# IQ_Demodulator.net
KiCad netlist of a schematic drawn in Altium Designer
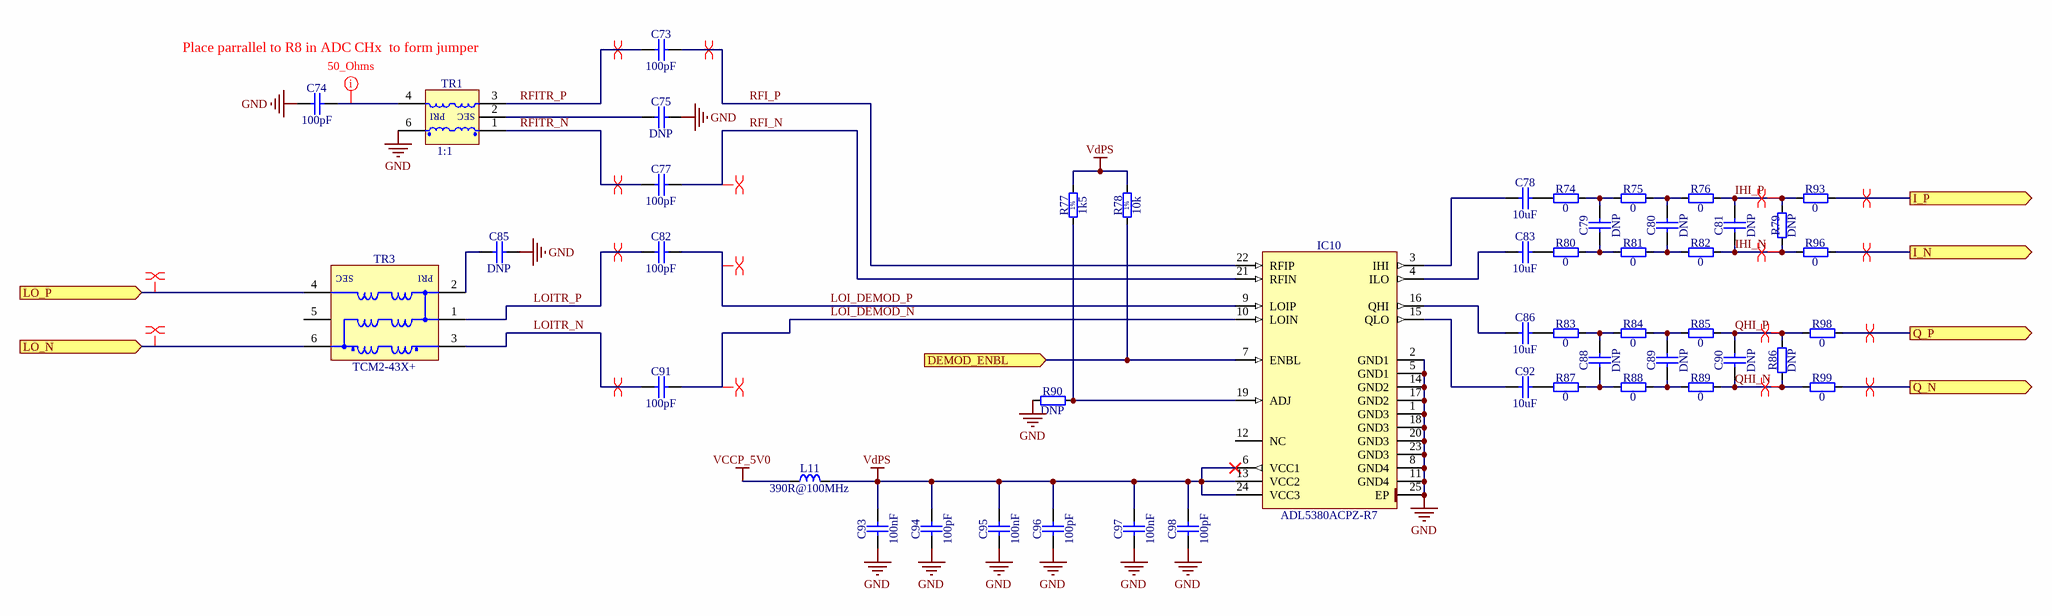
[diagram p0: IQ_Demodulator.SchDoc]

(export (version "E")
  (design (tool "Eeschema 10.0.6"))
  (components
    (comp (ref "C73")
      (value "100pF")
      (footprint "CAPC1005X55N")
      (description "Non-polarised capacitor")
      (fields
        (field (name "PART NUMBER") "CC0402_100PF_50V_5%_C0G")
        (field (name "VOLTAGE") "50V")
        (field (name "AUTHOR") "CERN DEM JLC")
      )
      (libsource (lib "Capacitors") (part "Capacitor - non polarized"))
    )
    (comp (ref "C74")
      (value "100pF")
      (footprint "CAPC1005X55N")
      (description "Non-polarised capacitor")
      (fields
        (field (name "PART NUMBER") "CC0402_100PF_50V_5%_C0G")
        (field (name "VOLTAGE") "50V")
        (field (name "AUTHOR") "CERN DEM JLC")
      )
      (libsource (lib "Capacitors") (part "Capacitor - non polarized"))
    )
    (comp (ref "C75")
      (value "DNP")
      (footprint "CAPC1005X55N")
      (description "Non-polarised capacitor")
      (fields
        (field (name "PART NUMBER") "CC0402_100PF_50V_5%_C0G")
        (field (name "VOLTAGE") "50V")
        (field (name "AUTHOR") "CERN DEM JLC")
      )
      (libsource (lib "Capacitors") (part "Capacitor - non polarized"))
    )
    (comp (ref "C77")
      (value "100pF")
      (footprint "CAPC1005X55N")
      (description "Non-polarised capacitor")
      (fields
        (field (name "PART NUMBER") "CC0402_100PF_50V_5%_C0G")
        (field (name "VOLTAGE") "50V")
        (field (name "AUTHOR") "CERN DEM JLC")
      )
      (libsource (lib "Capacitors") (part "Capacitor - non polarized"))
    )
    (comp (ref "C78")
      (value "10uF")
      (footprint "CAPC1005X70N")
      (description "Non-polarised capacitor")
      (fields
        (field (name "PART NUMBER") "CC0402_10UF_6.3V_20%_X5R")
        (field (name "VOLTAGE") "6.3V")
        (field (name "AUTHOR") "CERN DEM JLC")
      )
      (libsource (lib "Capacitors") (part "Capacitor - non polarized"))
    )
    (comp (ref "C79")
      (value "DNP")
      (footprint "CAPC1005X55N")
      (description "Non-polarised capacitor")
      (fields
        (field (name "PART NUMBER") "CC0402_1.5NF_50V_10%_X7R")
        (field (name "VOLTAGE") "50V")
        (field (name "AUTHOR") "CERN DEM JLC")
      )
      (libsource (lib "Capacitors") (part "Capacitor - non polarized"))
    )
    (comp (ref "C80")
      (value "DNP")
      (footprint "CAPC1005X55N")
      (description "Non-polarised capacitor")
      (fields
        (field (name "PART NUMBER") "CC0402_1.5NF_50V_10%_X7R")
        (field (name "VOLTAGE") "50V")
        (field (name "AUTHOR") "CERN DEM JLC")
      )
      (libsource (lib "Capacitors") (part "Capacitor - non polarized"))
    )
    (comp (ref "C81")
      (value "DNP")
      (footprint "CAPC1005X55N")
      (description "Non-polarised capacitor")
      (fields
        (field (name "PART NUMBER") "CC0402_1.5NF_50V_10%_X7R")
        (field (name "VOLTAGE") "50V")
        (field (name "AUTHOR") "CERN DEM JLC")
      )
      (libsource (lib "Capacitors") (part "Capacitor - non polarized"))
    )
    (comp (ref "C82")
      (value "100pF")
      (footprint "CAPC1005X55N")
      (description "Non-polarised capacitor")
      (fields
        (field (name "PART NUMBER") "CC0402_100PF_50V_5%_C0G")
        (field (name "VOLTAGE") "50V")
        (field (name "AUTHOR") "CERN DEM JLC")
      )
      (libsource (lib "Capacitors") (part "Capacitor - non polarized"))
    )
    (comp (ref "C83")
      (value "10uF")
      (footprint "CAPC1005X70N")
      (description "Non-polarised capacitor")
      (fields
        (field (name "PART NUMBER") "CC0402_10UF_6.3V_20%_X5R")
        (field (name "VOLTAGE") "6.3V")
        (field (name "AUTHOR") "CERN DEM JLC")
      )
      (libsource (lib "Capacitors") (part "Capacitor - non polarized"))
    )
    (comp (ref "C85")
      (value "DNP")
      (footprint "CAPC1005X55N")
      (description "Non-polarised capacitor")
      (fields
        (field (name "PART NUMBER") "CC0402_100PF_50V_5%_C0G")
        (field (name "VOLTAGE") "50V")
        (field (name "AUTHOR") "CERN DEM JLC")
      )
      (libsource (lib "Capacitors") (part "Capacitor - non polarized"))
    )
    (comp (ref "C86")
      (value "10uF")
      (footprint "CAPC1005X70N")
      (description "Non-polarised capacitor")
      (fields
        (field (name "PART NUMBER") "CC0402_10UF_6.3V_20%_X5R")
        (field (name "VOLTAGE") "6.3V")
        (field (name "AUTHOR") "CERN DEM JLC")
      )
      (libsource (lib "Capacitors") (part "Capacitor - non polarized"))
    )
    (comp (ref "C88")
      (value "DNP")
      (footprint "CAPC1005X55N")
      (description "Non-polarised capacitor")
      (fields
        (field (name "PART NUMBER") "CC0402_1.5NF_50V_10%_X7R")
        (field (name "VOLTAGE") "50V")
        (field (name "AUTHOR") "CERN DEM JLC")
      )
      (libsource (lib "Capacitors") (part "Capacitor - non polarized"))
    )
    (comp (ref "C89")
      (value "DNP")
      (footprint "CAPC1005X55N")
      (description "Non-polarised capacitor")
      (fields
        (field (name "PART NUMBER") "CC0402_1.5NF_50V_10%_X7R")
        (field (name "VOLTAGE") "50V")
        (field (name "AUTHOR") "CERN DEM JLC")
      )
      (libsource (lib "Capacitors") (part "Capacitor - non polarized"))
    )
    (comp (ref "C90")
      (value "DNP")
      (footprint "CAPC1005X55N")
      (description "Non-polarised capacitor")
      (fields
        (field (name "PART NUMBER") "CC0402_1.5NF_50V_10%_X7R")
        (field (name "VOLTAGE") "50V")
        (field (name "AUTHOR") "CERN DEM JLC")
      )
      (libsource (lib "Capacitors") (part "Capacitor - non polarized"))
    )
    (comp (ref "C91")
      (value "100pF")
      (footprint "CAPC1005X55N")
      (description "Non-polarised capacitor")
      (fields
        (field (name "PART NUMBER") "CC0402_100PF_50V_5%_C0G")
        (field (name "VOLTAGE") "50V")
        (field (name "AUTHOR") "CERN DEM JLC")
      )
      (libsource (lib "Capacitors") (part "Capacitor - non polarized"))
    )
    (comp (ref "C92")
      (value "10uF")
      (footprint "CAPC1005X70N")
      (description "Non-polarised capacitor")
      (fields
        (field (name "PART NUMBER") "CC0402_10UF_6.3V_20%_X5R")
        (field (name "VOLTAGE") "6.3V")
        (field (name "AUTHOR") "CERN DEM JLC")
      )
      (libsource (lib "Capacitors") (part "Capacitor - non polarized"))
    )
    (comp (ref "C93")
      (value "100nF")
      (footprint "CAPC1005X55N")
      (description "Non-polarised capacitor")
      (fields
        (field (name "PART NUMBER") "CC0402_100NF_16V_10%_X7R")
        (field (name "VOLTAGE") "16V")
        (field (name "AUTHOR") "CERN DEM JLC")
      )
      (libsource (lib "Capacitors") (part "Capacitor - non polarized"))
    )
    (comp (ref "C94")
      (value "100pF")
      (footprint "CAPC1005X55N")
      (description "Non-polarised capacitor")
      (fields
        (field (name "PART NUMBER") "CC0402_100PF_50V_5%_C0G")
        (field (name "VOLTAGE") "50V")
        (field (name "AUTHOR") "CERN DEM JLC")
      )
      (libsource (lib "Capacitors") (part "Capacitor - non polarized"))
    )
    (comp (ref "C95")
      (value "100nF")
      (footprint "CAPC1005X55N")
      (description "Non-polarised capacitor")
      (fields
        (field (name "PART NUMBER") "CC0402_100NF_16V_10%_X7R")
        (field (name "VOLTAGE") "16V")
        (field (name "AUTHOR") "CERN DEM JLC")
      )
      (libsource (lib "Capacitors") (part "Capacitor - non polarized"))
    )
    (comp (ref "C96")
      (value "100pF")
      (footprint "CAPC1005X55N")
      (description "Non-polarised capacitor")
      (fields
        (field (name "PART NUMBER") "CC0402_100PF_50V_5%_C0G")
        (field (name "VOLTAGE") "50V")
        (field (name "AUTHOR") "CERN DEM JLC")
      )
      (libsource (lib "Capacitors") (part "Capacitor - non polarized"))
    )
    (comp (ref "C97")
      (value "100nF")
      (footprint "CAPC1005X55N")
      (description "Non-polarised capacitor")
      (fields
        (field (name "PART NUMBER") "CC0402_100NF_16V_10%_X7R")
        (field (name "VOLTAGE") "16V")
        (field (name "AUTHOR") "CERN DEM JLC")
      )
      (libsource (lib "Capacitors") (part "Capacitor - non polarized"))
    )
    (comp (ref "C98")
      (value "100pF")
      (footprint "CAPC1005X55N")
      (description "Non-polarised capacitor")
      (fields
        (field (name "PART NUMBER") "CC0402_100PF_50V_5%_C0G")
        (field (name "VOLTAGE") "50V")
        (field (name "AUTHOR") "CERN DEM JLC")
      )
      (libsource (lib "Capacitors") (part "Capacitor - non polarized"))
    )
    (comp (ref "IC10")
      (value "ADL5380ACPZ-R7")
      (footprint "QFN50P400X400X100-25N-S265")
      (description "400 MHz to 6 GHz Quadrature Demodulator")
      (fields (field (name "MANUFACTURER") "ANALOG DEVICES") (field (name "AUTHOR") "CERN DEM JLC"))
      (libsource (lib "ICs And Semiconductors") (part "ADL5380"))
    )
    (comp (ref "L11")
      (value "390R@100MHz")
      (footprint "INDC1608X95N")
      (description "Inductor")
      (fields
        (field (name "PART NUMBER") "IND0603_TDK_MPZ1608R391A")
        (field (name "POWER") "1.2A")
        (field (name "AUTHOR") "CERN DEM JLC")
      )
      (libsource (lib "Inductors & Transformers") (part "Inductor"))
    )
    (comp (ref "R74")
      (value "0")
      (footprint "RESC1005X40N")
      (description "Resistor")
      (fields
        (field (name "PART NUMBER") "R0402_0R_JUMPER")
        (field (name "MANUFACTURER") "GENERIC")
        (field (name "AUTHOR") "CERN DEM JLC")
      )
      (libsource (lib "Resistors") (part "Resistor"))
    )
    (comp (ref "R75")
      (value "0")
      (footprint "RESC1005X40N")
      (description "Resistor")
      (fields
        (field (name "PART NUMBER") "R0402_0R_JUMPER")
        (field (name "MANUFACTURER") "GENERIC")
        (field (name "AUTHOR") "CERN DEM JLC")
      )
      (libsource (lib "Resistors") (part "Resistor"))
    )
    (comp (ref "R76")
      (value "0")
      (footprint "RESC1005X40N")
      (description "Resistor")
      (fields
        (field (name "PART NUMBER") "R0402_0R_JUMPER")
        (field (name "MANUFACTURER") "GENERIC")
        (field (name "AUTHOR") "CERN DEM JLC")
      )
      (libsource (lib "Resistors") (part "Resistor"))
    )
    (comp (ref "R77")
      (value "1k5")
      (footprint "RESC1005X40N")
      (description "Resistor - 1%")
      (fields
        (field (name "PART NUMBER") "R0402_1K5_1%_0.0625W_100PPM")
        (field (name "POWER") "0.0625W")
        (field (name "AUTHOR") "CERN DEM JLC")
      )
      (libsource (lib "Resistors") (part "Resistor - 1%"))
    )
    (comp (ref "R78")
      (value "10k")
      (footprint "RESC1005X40N")
      (description "Resistor - 1%")
      (fields
        (field (name "PART NUMBER") "R0402_10K_1%_0.0625W_100PPM")
        (field (name "POWER") "0.0625W")
        (field (name "AUTHOR") "CERN DEM JLC")
      )
      (libsource (lib "Resistors") (part "Resistor - 1%"))
    )
    (comp (ref "R79")
      (value "DNP")
      (footprint "RESC1005X40N")
      (description "Resistor")
      (fields
        (field (name "PART NUMBER") "R0402_0R_JUMPER")
        (field (name "MANUFACTURER") "GENERIC")
        (field (name "AUTHOR") "CERN DEM JLC")
      )
      (libsource (lib "Resistors") (part "Resistor"))
    )
    (comp (ref "R80")
      (value "0")
      (footprint "RESC1005X40N")
      (description "Resistor")
      (fields
        (field (name "PART NUMBER") "R0402_0R_JUMPER")
        (field (name "MANUFACTURER") "GENERIC")
        (field (name "AUTHOR") "CERN DEM JLC")
      )
      (libsource (lib "Resistors") (part "Resistor"))
    )
    (comp (ref "R81")
      (value "0")
      (footprint "RESC1005X40N")
      (description "Resistor")
      (fields
        (field (name "PART NUMBER") "R0402_0R_JUMPER")
        (field (name "MANUFACTURER") "GENERIC")
        (field (name "AUTHOR") "CERN DEM JLC")
      )
      (libsource (lib "Resistors") (part "Resistor"))
    )
    (comp (ref "R82")
      (value "0")
      (footprint "RESC1005X40N")
      (description "Resistor")
      (fields
        (field (name "PART NUMBER") "R0402_0R_JUMPER")
        (field (name "MANUFACTURER") "GENERIC")
        (field (name "AUTHOR") "CERN DEM JLC")
      )
      (libsource (lib "Resistors") (part "Resistor"))
    )
    (comp (ref "R83")
      (value "0")
      (footprint "RESC1005X40N")
      (description "Resistor")
      (fields
        (field (name "PART NUMBER") "R0402_0R_JUMPER")
        (field (name "MANUFACTURER") "GENERIC")
        (field (name "AUTHOR") "CERN DEM JLC")
      )
      (libsource (lib "Resistors") (part "Resistor"))
    )
    (comp (ref "R84")
      (value "0")
      (footprint "RESC1005X40N")
      (description "Resistor")
      (fields
        (field (name "PART NUMBER") "R0402_0R_JUMPER")
        (field (name "MANUFACTURER") "GENERIC")
        (field (name "AUTHOR") "CERN DEM JLC")
      )
      (libsource (lib "Resistors") (part "Resistor"))
    )
    (comp (ref "R85")
      (value "0")
      (footprint "RESC1005X40N")
      (description "Resistor")
      (fields
        (field (name "PART NUMBER") "R0402_0R_JUMPER")
        (field (name "MANUFACTURER") "GENERIC")
        (field (name "AUTHOR") "CERN DEM JLC")
      )
      (libsource (lib "Resistors") (part "Resistor"))
    )
    (comp (ref "R86")
      (value "DNP")
      (footprint "RESC1005X40N")
      (description "Resistor")
      (fields
        (field (name "PART NUMBER") "R0402_0R_JUMPER")
        (field (name "MANUFACTURER") "GENERIC")
        (field (name "AUTHOR") "CERN DEM JLC")
      )
      (libsource (lib "Resistors") (part "Resistor"))
    )
    (comp (ref "R87")
      (value "0")
      (footprint "RESC1005X40N")
      (description "Resistor")
      (fields
        (field (name "PART NUMBER") "R0402_0R_JUMPER")
        (field (name "MANUFACTURER") "GENERIC")
        (field (name "AUTHOR") "CERN DEM JLC")
      )
      (libsource (lib "Resistors") (part "Resistor"))
    )
    (comp (ref "R88")
      (value "0")
      (footprint "RESC1005X40N")
      (description "Resistor")
      (fields
        (field (name "PART NUMBER") "R0402_0R_JUMPER")
        (field (name "MANUFACTURER") "GENERIC")
        (field (name "AUTHOR") "CERN DEM JLC")
      )
      (libsource (lib "Resistors") (part "Resistor"))
    )
    (comp (ref "R89")
      (value "0")
      (footprint "RESC1005X40N")
      (description "Resistor")
      (fields
        (field (name "PART NUMBER") "R0402_0R_JUMPER")
        (field (name "MANUFACTURER") "GENERIC")
        (field (name "AUTHOR") "CERN DEM JLC")
      )
      (libsource (lib "Resistors") (part "Resistor"))
    )
    (comp (ref "R90")
      (value "DNP")
      (footprint "RESC1005X40N")
      (description "Resistor")
      (fields
        (field (name "PART NUMBER") "R0402_0R_JUMPER")
        (field (name "MANUFACTURER") "GENERIC")
        (field (name "AUTHOR") "CERN DEM JLC")
      )
      (libsource (lib "Resistors") (part "Resistor"))
    )
    (comp (ref "R93")
      (value "0")
      (footprint "RESC1005X40N")
      (description "Resistor")
      (fields
        (field (name "PART NUMBER") "R0402_0R_JUMPER")
        (field (name "MANUFACTURER") "GENERIC")
        (field (name "AUTHOR") "CERN DEM JLC")
      )
      (libsource (lib "Resistors") (part "Resistor"))
    )
    (comp (ref "R96")
      (value "0")
      (footprint "RESC1005X40N")
      (description "Resistor")
      (fields
        (field (name "PART NUMBER") "R0402_0R_JUMPER")
        (field (name "MANUFACTURER") "GENERIC")
        (field (name "AUTHOR") "CERN DEM JLC")
      )
      (libsource (lib "Resistors") (part "Resistor"))
    )
    (comp (ref "R98")
      (value "0")
      (footprint "RESC1005X40N")
      (description "Resistor")
      (fields
        (field (name "PART NUMBER") "R0402_0R_JUMPER")
        (field (name "MANUFACTURER") "GENERIC")
        (field (name "AUTHOR") "CERN DEM JLC")
      )
      (libsource (lib "Resistors") (part "Resistor"))
    )
    (comp (ref "R99")
      (value "0")
      (footprint "RESC1005X40N")
      (description "Resistor")
      (fields
        (field (name "PART NUMBER") "R0402_0R_JUMPER")
        (field (name "MANUFACTURER") "GENERIC")
        (field (name "AUTHOR") "CERN DEM JLC")
      )
      (libsource (lib "Resistors") (part "Resistor"))
    )
    (comp (ref "TR1")
      (value "1:1")
      (footprint "XFMR_MINI-CIRCUITS_AT1521")
      (description "50 Ohms 650 To 4000MHz RF Transformer")
      (fields
        (field (name "PART NUMBER") "XFMR_MINI-CIRCUITS_TC1-1-43X+")
        (field (name "MANUFACTURER") "MINI-CIRCUITS")
        (field (name "AUTHOR") "CERN DEM JMW")
      )
      (libsource (lib "Inductors & Transformers") (part "XFMR_MINI-CIRCUITS_TC1-1-43X+"))
    )
    (comp (ref "TR3")
      (value "TCM2-43X+")
      (footprint "XFMR_MINI-CIRCUITS_DB1627")
      (description "50 OHMS 10 to 4000 MHz RF Transformer")
      (fields
        (field (name "PART NUMBER") "XFMR_MINI-CIRCUITS_TCM2-43X+")
        (field (name "POWER") "0.4W")
        (field (name "AUTHOR") "CERN DEM BC")
      )
      (libsource (lib "Inductors & Transformers") (part "XFMR_MINI-CIRCUITS_TCM2-43X"))
    )
  )
  (nets
    (net (code "1") (name "/DEMOD_ENBL") (class "Default")
      (node (ref "IC10") (pin "7") (pinfunction "ENBL_7") (pintype "input"))
      (node (ref "R78") (pin "1") (pinfunction "1_1") (pintype "passive"))
    )
    (net (code "2") (name "/IHI_N") (class "Default")
      (node (ref "C81") (pin "1") (pinfunction "1_1") (pintype "passive"))
      (node (ref "R79") (pin "1") (pinfunction "1_1") (pintype "passive"))
      (node (ref "R82") (pin "2") (pinfunction "2_2") (pintype "passive"))
      (node (ref "R96") (pin "1") (pinfunction "1_1") (pintype "passive"))
    )
    (net (code "3") (name "/IHI_P") (class "Default")
      (node (ref "C81") (pin "2") (pinfunction "2_2") (pintype "passive"))
      (node (ref "R76") (pin "2") (pinfunction "2_2") (pintype "passive"))
      (node (ref "R79") (pin "2") (pinfunction "2_2") (pintype "passive"))
      (node (ref "R93") (pin "1") (pinfunction "1_1") (pintype "passive"))
    )
    (net (code "4") (name "/I_N") (class "Default")
      (node (ref "R96") (pin "2") (pinfunction "2_2") (pintype "passive"))
    )
    (net (code "5") (name "/I_P") (class "Default")
      (node (ref "R93") (pin "2") (pinfunction "2_2") (pintype "passive"))
    )
    (net (code "6") (name "/LOITR_N") (class "Default")
      (node (ref "C91") (pin "1") (pinfunction "1_1") (pintype "passive"))
      (node (ref "TR3") (pin "3") (pinfunction "P1_3") (pintype "passive"))
    )
    (net (code "7") (name "/LOITR_P") (class "Default")
      (node (ref "C82") (pin "1") (pinfunction "1_1") (pintype "passive"))
      (node (ref "TR3") (pin "1") (pinfunction "P1_1") (pintype "passive"))
    )
    (net (code "8") (name "/LOI_DEMOD_N") (class "Default")
      (node (ref "C91") (pin "2") (pinfunction "2_2") (pintype "passive"))
      (node (ref "IC10") (pin "10") (pinfunction "LOIN_10") (pintype "input"))
    )
    (net (code "9") (name "/LOI_DEMOD_P") (class "Default")
      (node (ref "C82") (pin "2") (pinfunction "2_2") (pintype "passive"))
      (node (ref "IC10") (pin "9") (pinfunction "LOIP_9") (pintype "input"))
    )
    (net (code "10") (name "/LO_N") (class "Default")
      (node (ref "TR3") (pin "6") (pinfunction "S1_6") (pintype "passive"))
    )
    (net (code "11") (name "/LO_P") (class "Default")
      (node (ref "TR3") (pin "4") (pinfunction "S1_4") (pintype "passive"))
    )
    (net (code "12") (name "/QHI_N") (class "Default")
      (node (ref "C90") (pin "1") (pinfunction "1_1") (pintype "passive"))
      (node (ref "R86") (pin "1") (pinfunction "1_1") (pintype "passive"))
      (node (ref "R89") (pin "2") (pinfunction "2_2") (pintype "passive"))
      (node (ref "R99") (pin "1") (pinfunction "1_1") (pintype "passive"))
    )
    (net (code "13") (name "/QHI_P") (class "Default")
      (node (ref "C90") (pin "2") (pinfunction "2_2") (pintype "passive"))
      (node (ref "R85") (pin "2") (pinfunction "2_2") (pintype "passive"))
      (node (ref "R86") (pin "2") (pinfunction "2_2") (pintype "passive"))
      (node (ref "R98") (pin "1") (pinfunction "1_1") (pintype "passive"))
    )
    (net (code "14") (name "/Q_N") (class "Default")
      (node (ref "R99") (pin "2") (pinfunction "2_2") (pintype "passive"))
    )
    (net (code "15") (name "/Q_P") (class "Default")
      (node (ref "R98") (pin "2") (pinfunction "2_2") (pintype "passive"))
    )
    (net (code "16") (name "/RFITR_N") (class "Default")
      (node (ref "C77") (pin "1") (pinfunction "1_1") (pintype "passive"))
      (node (ref "TR1") (pin "1") (pinfunction "SDOT_1") (pintype "passive"))
    )
    (net (code "17") (name "/RFITR_P") (class "Default")
      (node (ref "C73") (pin "1") (pinfunction "1_1") (pintype "passive"))
      (node (ref "TR1") (pin "3") (pinfunction "S_3") (pintype "passive"))
    )
    (net (code "18") (name "/RFI_N") (class "Default")
      (node (ref "C77") (pin "2") (pinfunction "2_2") (pintype "passive"))
      (node (ref "IC10") (pin "21") (pinfunction "RFIN_21") (pintype "input"))
    )
    (net (code "19") (name "/RFI_P") (class "Default")
      (node (ref "C73") (pin "2") (pinfunction "2_2") (pintype "passive"))
      (node (ref "IC10") (pin "22") (pinfunction "RFIP_22") (pintype "input"))
    )
    (net (code "20") (name "GND") (class "Default")
      (node (ref "C74") (pin "1") (pinfunction "1_1") (pintype "passive"))
      (node (ref "C75") (pin "2") (pinfunction "2_2") (pintype "passive"))
      (node (ref "C85") (pin "2") (pinfunction "2_2") (pintype "passive"))
      (node (ref "C93") (pin "1") (pinfunction "1_1") (pintype "passive"))
      (node (ref "C94") (pin "1") (pinfunction "1_1") (pintype "passive"))
      (node (ref "C95") (pin "1") (pinfunction "1_1") (pintype "passive"))
      (node (ref "C96") (pin "1") (pinfunction "1_1") (pintype "passive"))
      (node (ref "C97") (pin "1") (pinfunction "1_1") (pintype "passive"))
      (node (ref "C98") (pin "1") (pinfunction "1_1") (pintype "passive"))
      (node (ref "IC10") (pin "1") (pinfunction "GND3_1") (pintype "power_in"))
      (node (ref "IC10") (pin "11") (pinfunction "GND4_11") (pintype "power_in"))
      (node (ref "IC10") (pin "14") (pinfunction "GND2_14") (pintype "power_in"))
      (node (ref "IC10") (pin "17") (pinfunction "GND2_17") (pintype "power_in"))
      (node (ref "IC10") (pin "18") (pinfunction "GND3_18") (pintype "power_in"))
      (node (ref "IC10") (pin "2") (pinfunction "GND1_2") (pintype "power_in"))
      (node (ref "IC10") (pin "20") (pinfunction "GND3_20") (pintype "power_in"))
      (node (ref "IC10") (pin "23") (pinfunction "GND3_23") (pintype "power_in"))
      (node (ref "IC10") (pin "25") (pinfunction "EP_25") (pintype "power_in"))
      (node (ref "IC10") (pin "5") (pinfunction "GND1_5") (pintype "power_in"))
      (node (ref "IC10") (pin "8") (pinfunction "GND4_8") (pintype "power_in"))
      (node (ref "R90") (pin "1") (pinfunction "1_1") (pintype "passive"))
      (node (ref "TR1") (pin "6") (pinfunction "PDOT_6") (pintype "passive"))
    )
    (net (code "21") (name "Net-(C78-Pad2)") (class "Default")
      (node (ref "C78") (pin "2") (pinfunction "2_2") (pintype "passive"))
      (node (ref "R74") (pin "1") (pinfunction "1_1") (pintype "passive"))
    )
    (net (code "22") (name "Net-(C79-Pad1)") (class "Default")
      (node (ref "C79") (pin "1") (pinfunction "1_1") (pintype "passive"))
      (node (ref "R80") (pin "2") (pinfunction "2_2") (pintype "passive"))
      (node (ref "R81") (pin "1") (pinfunction "1_1") (pintype "passive"))
    )
    (net (code "23") (name "Net-(C79-Pad2)") (class "Default")
      (node (ref "C79") (pin "2") (pinfunction "2_2") (pintype "passive"))
      (node (ref "R74") (pin "2") (pinfunction "2_2") (pintype "passive"))
      (node (ref "R75") (pin "1") (pinfunction "1_1") (pintype "passive"))
    )
    (net (code "24") (name "Net-(C80-Pad1)") (class "Default")
      (node (ref "C80") (pin "1") (pinfunction "1_1") (pintype "passive"))
      (node (ref "R81") (pin "2") (pinfunction "2_2") (pintype "passive"))
      (node (ref "R82") (pin "1") (pinfunction "1_1") (pintype "passive"))
    )
    (net (code "25") (name "Net-(C80-Pad2)") (class "Default")
      (node (ref "C80") (pin "2") (pinfunction "2_2") (pintype "passive"))
      (node (ref "R75") (pin "2") (pinfunction "2_2") (pintype "passive"))
      (node (ref "R76") (pin "1") (pinfunction "1_1") (pintype "passive"))
    )
    (net (code "26") (name "Net-(C83-Pad2)") (class "Default")
      (node (ref "C83") (pin "2") (pinfunction "2_2") (pintype "passive"))
      (node (ref "R80") (pin "1") (pinfunction "1_1") (pintype "passive"))
    )
    (net (code "27") (name "Net-(C85-Pad1)") (class "Default")
      (node (ref "C85") (pin "1") (pinfunction "1_1") (pintype "passive"))
      (node (ref "TR3") (pin "2") (pinfunction "P1_2") (pintype "passive"))
    )
    (net (code "28") (name "Net-(C86-Pad2)") (class "Default")
      (node (ref "C86") (pin "2") (pinfunction "2_2") (pintype "passive"))
      (node (ref "R83") (pin "1") (pinfunction "1_1") (pintype "passive"))
    )
    (net (code "29") (name "Net-(C88-Pad1)") (class "Default")
      (node (ref "C88") (pin "1") (pinfunction "1_1") (pintype "passive"))
      (node (ref "R87") (pin "2") (pinfunction "2_2") (pintype "passive"))
      (node (ref "R88") (pin "1") (pinfunction "1_1") (pintype "passive"))
    )
    (net (code "30") (name "Net-(C88-Pad2)") (class "Default")
      (node (ref "C88") (pin "2") (pinfunction "2_2") (pintype "passive"))
      (node (ref "R83") (pin "2") (pinfunction "2_2") (pintype "passive"))
      (node (ref "R84") (pin "1") (pinfunction "1_1") (pintype "passive"))
    )
    (net (code "31") (name "Net-(C89-Pad1)") (class "Default")
      (node (ref "C89") (pin "1") (pinfunction "1_1") (pintype "passive"))
      (node (ref "R88") (pin "2") (pinfunction "2_2") (pintype "passive"))
      (node (ref "R89") (pin "1") (pinfunction "1_1") (pintype "passive"))
    )
    (net (code "32") (name "Net-(C89-Pad2)") (class "Default")
      (node (ref "C89") (pin "2") (pinfunction "2_2") (pintype "passive"))
      (node (ref "R84") (pin "2") (pinfunction "2_2") (pintype "passive"))
      (node (ref "R85") (pin "1") (pinfunction "1_1") (pintype "passive"))
    )
    (net (code "33") (name "Net-(C92-Pad2)") (class "Default")
      (node (ref "C92") (pin "2") (pinfunction "2_2") (pintype "passive"))
      (node (ref "R87") (pin "1") (pinfunction "1_1") (pintype "passive"))
    )
    (net (code "34") (name "Net-(IC10-ADJ)") (class "Default")
      (node (ref "IC10") (pin "19") (pinfunction "ADJ_19") (pintype "input"))
      (node (ref "R77") (pin "1") (pinfunction "1_1") (pintype "passive"))
      (node (ref "R90") (pin "2") (pinfunction "2_2") (pintype "passive"))
    )
    (net (code "35") (name "Net-(IC10-IHI)") (class "Default")
      (node (ref "C78") (pin "1") (pinfunction "1_1") (pintype "passive"))
      (node (ref "IC10") (pin "3") (pinfunction "IHI_3") (pintype "output"))
    )
    (net (code "36") (name "Net-(IC10-ILO)") (class "Default")
      (node (ref "C83") (pin "1") (pinfunction "1_1") (pintype "passive"))
      (node (ref "IC10") (pin "4") (pinfunction "ILO_4") (pintype "output"))
    )
    (net (code "37") (name "Net-(IC10-QHI)") (class "Default")
      (node (ref "C86") (pin "1") (pinfunction "1_1") (pintype "passive"))
      (node (ref "IC10") (pin "16") (pinfunction "QHI_16") (pintype "output"))
    )
    (net (code "38") (name "Net-(IC10-QLO)") (class "Default")
      (node (ref "C92") (pin "1") (pinfunction "1_1") (pintype "passive"))
      (node (ref "IC10") (pin "15") (pinfunction "QLO_15") (pintype "output"))
    )
    (net (code "39") (name "Net-(TR1-NC)") (class "Default")
      (node (ref "C75") (pin "1") (pinfunction "1_1") (pintype "passive"))
      (node (ref "TR1") (pin "2") (pinfunction "NC_2") (pintype "passive"))
    )
    (net (code "40") (name "Net-(TR1-P)") (class "Default")
      (node (ref "C74") (pin "2") (pinfunction "2_2") (pintype "passive"))
      (node (ref "TR1") (pin "4") (pinfunction "P_4") (pintype "passive"))
    )
    (net (code "41") (name "VCCP_5V0") (class "Default")
      (node (ref "L11") (pin "1") (pinfunction "1_1") (pintype "passive"))
    )
    (net (code "42") (name "VdPS") (class "Default")
      (node (ref "C93") (pin "2") (pinfunction "2_2") (pintype "passive"))
      (node (ref "C94") (pin "2") (pinfunction "2_2") (pintype "passive"))
      (node (ref "C95") (pin "2") (pinfunction "2_2") (pintype "passive"))
      (node (ref "C96") (pin "2") (pinfunction "2_2") (pintype "passive"))
      (node (ref "C97") (pin "2") (pinfunction "2_2") (pintype "passive"))
      (node (ref "C98") (pin "2") (pinfunction "2_2") (pintype "passive"))
      (node (ref "IC10") (pin "13") (pinfunction "VCC2_13") (pintype "power_in"))
      (node (ref "IC10") (pin "24") (pinfunction "VCC3_24") (pintype "power_in"))
      (node (ref "IC10") (pin "6") (pinfunction "VCC1_6") (pintype "output"))
      (node (ref "L11") (pin "2") (pinfunction "2_2") (pintype "passive"))
      (node (ref "R77") (pin "2") (pinfunction "2_2") (pintype "passive"))
      (node (ref "R78") (pin "2") (pinfunction "2_2") (pintype "passive"))
    )
    (net (code "43") (name "unconnected-(IC10-NC-Pad12)") (class "Default")
      (node (ref "IC10") (pin "12") (pinfunction "NC_12") (pintype "passive"))
    )
    (net (code "44") (name "unconnected-(TR3-NC-Pad5)") (class "Default")
      (node (ref "TR3") (pin "5") (pinfunction "NC_5") (pintype "passive"))
    )
  )
)
